# v1_5_IMU_Baro.net
KiCad netlist of a schematic drawn in Altium Designer
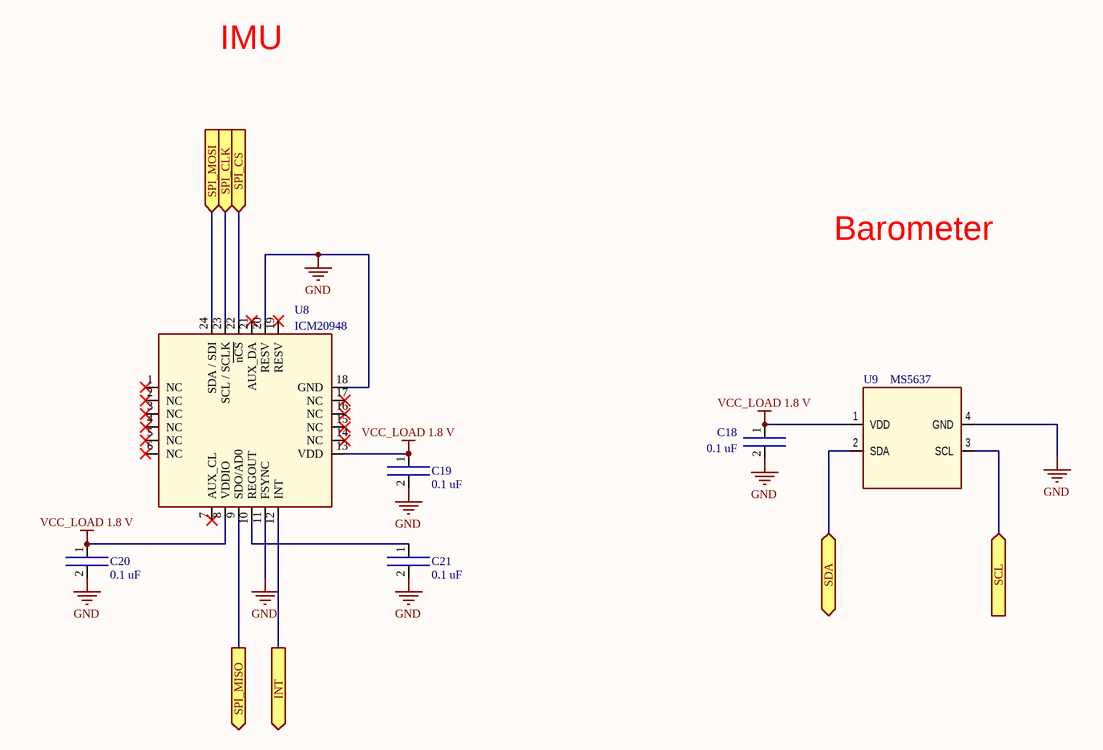
[diagram p0: v1.5 IMU & Baro.SchDoc]

(export (version "E")
  (design (tool "Eeschema 10.0.6"))
  (components
    (comp (ref "C18")
      (value "0.1 uF")
      (footprint "Ungravity Library:0402")
      (libsource (lib "Ungravity Library") (part "Capasistor"))
    )
    (comp (ref "C19")
      (value "0.1 uF")
      (footprint "Ungravity Library:0402")
      (libsource (lib "Ungravity Library") (part "Capasistor"))
    )
    (comp (ref "C20")
      (value "0.1 uF")
      (footprint "Ungravity Library:0402")
      (libsource (lib "Ungravity Library") (part "Capasistor"))
    )
    (comp (ref "C21")
      (value "0.1 uF")
      (footprint "Ungravity Library:0402")
      (libsource (lib "Ungravity Library") (part "Capasistor"))
    )
    (comp (ref "U8")
      (value "ICM20948")
      (footprint "Ungravity Library:ICM20948")
      (libsource (lib "Ungravity Library") (part "ICM20948"))
    )
    (comp (ref "U9")
      (value "MS5637")
      (footprint "Ungravity Library:MS5637-02BA03")
      (libsource (lib "Ungravity Library") (part "MS5637-02BA03"))
    )
  )
  (nets
    (net (code "1") (name "/INT") (class "Default")
      (node (ref "U8") (pin "12") (pinfunction "INT_12") (pintype "passive"))
    )
    (net (code "2") (name "/SCL") (class "Default")
      (node (ref "U9") (pin "3") (pinfunction "SCL_3") (pintype "passive"))
    )
    (net (code "3") (name "/SDA") (class "Default")
      (node (ref "U9") (pin "2") (pinfunction "SDA_2") (pintype "passive"))
    )
    (net (code "4") (name "/SPI_CLK") (class "Default")
      (node (ref "U8") (pin "23") (pinfunction "SCL_/_SCLK_23") (pintype "passive"))
    )
    (net (code "5") (name "/SPI_CS") (class "Default")
      (node (ref "U8") (pin "22") (pinfunction "~{nCS}_22") (pintype "passive"))
    )
    (net (code "6") (name "/SPI_MISO") (class "Default")
      (node (ref "U8") (pin "9") (pinfunction "SDO/AD0_9") (pintype "passive"))
    )
    (net (code "7") (name "/SPI_MOSI") (class "Default")
      (node (ref "U8") (pin "24") (pinfunction "SDA_/_SDI_24") (pintype "passive"))
    )
    (net (code "8") (name "GND") (class "Default")
      (node (ref "C18") (pin "2") (pinfunction "2_2") (pintype "passive"))
      (node (ref "C19") (pin "2") (pinfunction "2_2") (pintype "passive"))
      (node (ref "C20") (pin "2") (pinfunction "2_2") (pintype "passive"))
      (node (ref "C21") (pin "2") (pinfunction "2_2") (pintype "passive"))
      (node (ref "U8") (pin "11") (pinfunction "FSYNC_11") (pintype "passive"))
      (node (ref "U8") (pin "18") (pinfunction "GND_18") (pintype "passive"))
      (node (ref "U8") (pin "20") (pinfunction "RESV_20") (pintype "passive"))
      (node (ref "U9") (pin "4") (pinfunction "GND_4") (pintype "passive"))
    )
    (net (code "9") (name "Net-(U8-REGOUT)") (class "Default")
      (node (ref "C21") (pin "1") (pinfunction "1_1") (pintype "passive"))
      (node (ref "U8") (pin "10") (pinfunction "REGOUT_10") (pintype "passive"))
    )
    (net (code "10") (name "VCC_LOAD 1.8 V") (class "Default")
      (node (ref "C18") (pin "1") (pinfunction "1_1") (pintype "passive"))
      (node (ref "C19") (pin "1") (pinfunction "1_1") (pintype "passive"))
      (node (ref "C20") (pin "1") (pinfunction "1_1") (pintype "passive"))
      (node (ref "U8") (pin "13") (pinfunction "VDD_13") (pintype "passive"))
      (node (ref "U8") (pin "8") (pinfunction "VDDIO_8") (pintype "passive"))
      (node (ref "U9") (pin "1") (pinfunction "VDD_1") (pintype "passive"))
    )
    (net (code "11") (name "unconnected-(U8-AUX_CL-Pad7)") (class "Default")
      (node (ref "U8") (pin "7") (pinfunction "AUX_CL_7") (pintype "passive+no_connect"))
    )
    (net (code "12") (name "unconnected-(U8-AUX_DA-Pad21)") (class "Default")
      (node (ref "U8") (pin "21") (pinfunction "AUX_DA_21") (pintype "passive+no_connect"))
    )
    (net (code "13") (name "unconnected-(U8-NC-Pad1)") (class "Default")
      (node (ref "U8") (pin "1") (pinfunction "NC_1") (pintype "passive+no_connect"))
    )
    (net (code "14") (name "unconnected-(U8-NC-Pad2)") (class "Default")
      (node (ref "U8") (pin "2") (pinfunction "NC_2") (pintype "passive+no_connect"))
    )
    (net (code "15") (name "unconnected-(U8-NC-Pad3)") (class "Default")
      (node (ref "U8") (pin "3") (pinfunction "NC_3") (pintype "passive+no_connect"))
    )
    (net (code "16") (name "unconnected-(U8-NC-Pad4)") (class "Default")
      (node (ref "U8") (pin "4") (pinfunction "NC_4") (pintype "passive+no_connect"))
    )
    (net (code "17") (name "unconnected-(U8-NC-Pad5)") (class "Default")
      (node (ref "U8") (pin "5") (pinfunction "NC_5") (pintype "passive+no_connect"))
    )
    (net (code "18") (name "unconnected-(U8-NC-Pad6)") (class "Default")
      (node (ref "U8") (pin "6") (pinfunction "NC_6") (pintype "passive+no_connect"))
    )
    (net (code "19") (name "unconnected-(U8-NC-Pad14)") (class "Default")
      (node (ref "U8") (pin "14") (pinfunction "NC_14") (pintype "passive+no_connect"))
    )
    (net (code "20") (name "unconnected-(U8-NC-Pad15)") (class "Default")
      (node (ref "U8") (pin "15") (pinfunction "NC_15") (pintype "passive+no_connect"))
    )
    (net (code "21") (name "unconnected-(U8-NC-Pad16)") (class "Default")
      (node (ref "U8") (pin "16") (pinfunction "NC_16") (pintype "passive+no_connect"))
    )
    (net (code "22") (name "unconnected-(U8-NC-Pad17)") (class "Default")
      (node (ref "U8") (pin "17") (pinfunction "NC_17") (pintype "passive+no_connect"))
    )
    (net (code "23") (name "unconnected-(U8-RESV-Pad19)") (class "Default")
      (node (ref "U8") (pin "19") (pinfunction "RESV_19") (pintype "passive+no_connect"))
    )
  )
)
